# PDM-S11-V00-IMU.net
KiCad netlist of a schematic drawn in Altium Designer
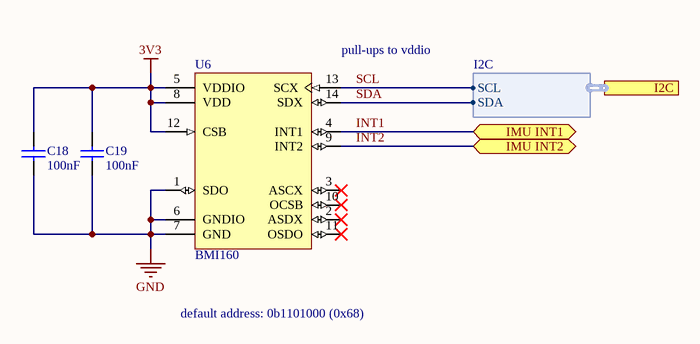
[diagram p0: PDM-S11-V00-IMU.SchDoc]

(export (version "E")
  (design (tool "Eeschema 10.0.6"))
  (components
    (comp (ref "C18")
      (value "100nF")
      (footprint "Cap_Ceramic_0603")
      (description "Capacitor, Ceramic, SMD, 100nF, 50V, 5%, X7R, 0603")
      (libsource (lib "StandardCapacitors") (part "100nF 50V 5% X7R 0603"))
    )
    (comp (ref "C19")
      (value "100nF")
      (footprint "Cap_Ceramic_0603")
      (description "Capacitor, Ceramic, SMD, 100nF, 50V, 5%, X7R, 0603")
      (libsource (lib "StandardCapacitors") (part "100nF 50V 5% X7R 0603"))
    )
    (comp (ref "U6")
      (value "BMI160")
      (footprint "BOSC-BMI160_V")
      (fields (field (name "MANUFACTURER") "Bosch"))
      (libsource (lib "QUTMS_IMULibrary") (part "BMI160"))
    )
  )
  (nets
    (net (code "2") (name "/INT1") (class "Default")
      (node (ref "U6") (pin "4") (pinfunction "INT1_4") (pintype "bidirectional"))
    )
    (net (code "3") (name "/INT2") (class "Default")
      (node (ref "U6") (pin "9") (pinfunction "INT2_9") (pintype "bidirectional"))
    )
    (net (code "4") (name "/SCL") (class "Default")
      (node (ref "U6") (pin "13") (pinfunction "SCX_13") (pintype "input"))
    )
    (net (code "5") (name "/SDA") (class "Default")
      (node (ref "U6") (pin "14") (pinfunction "SDX_14") (pintype "bidirectional"))
    )
    (net (code "7") (name "3V3") (class "Default")
      (node (ref "C18") (pin "2") (pinfunction "2_2") (pintype "passive"))
      (node (ref "C19") (pin "2") (pinfunction "2_2") (pintype "passive"))
      (node (ref "U6") (pin "12") (pinfunction "CSB_12") (pintype "input"))
      (node (ref "U6") (pin "5") (pinfunction "VDDIO_5") (pintype "power_in"))
      (node (ref "U6") (pin "8") (pinfunction "VDD_8") (pintype "power_in"))
    )
    (net (code "8") (name "GND") (class "Default")
      (node (ref "C18") (pin "1") (pinfunction "1_1") (pintype "passive"))
      (node (ref "C19") (pin "1") (pinfunction "1_1") (pintype "passive"))
      (node (ref "U6") (pin "1") (pinfunction "SDO_1") (pintype "bidirectional"))
      (node (ref "U6") (pin "6") (pinfunction "GNDIO_6") (pintype "power_in"))
      (node (ref "U6") (pin "7") (pinfunction "GND_7") (pintype "power_in"))
    )
    (net (code "9") (name "unconnected-(U6-ASCX-Pad3)") (class "Default")
      (node (ref "U6") (pin "3") (pinfunction "ASCX_3") (pintype "bidirectional+no_connect"))
    )
    (net (code "10") (name "unconnected-(U6-ASDX-Pad2)") (class "Default")
      (node (ref "U6") (pin "2") (pinfunction "ASDX_2") (pintype "bidirectional+no_connect"))
    )
    (net (code "11") (name "unconnected-(U6-OCSB-Pad10)") (class "Default")
      (node (ref "U6") (pin "10") (pinfunction "OCSB_10") (pintype "bidirectional+no_connect"))
    )
    (net (code "12") (name "unconnected-(U6-OSDO-Pad11)") (class "Default")
      (node (ref "U6") (pin "11") (pinfunction "OSDO_11") (pintype "bidirectional+no_connect"))
    )
  )
)
